# F1-chip.net
KiCad netlist of a schematic drawn in Altium Designer
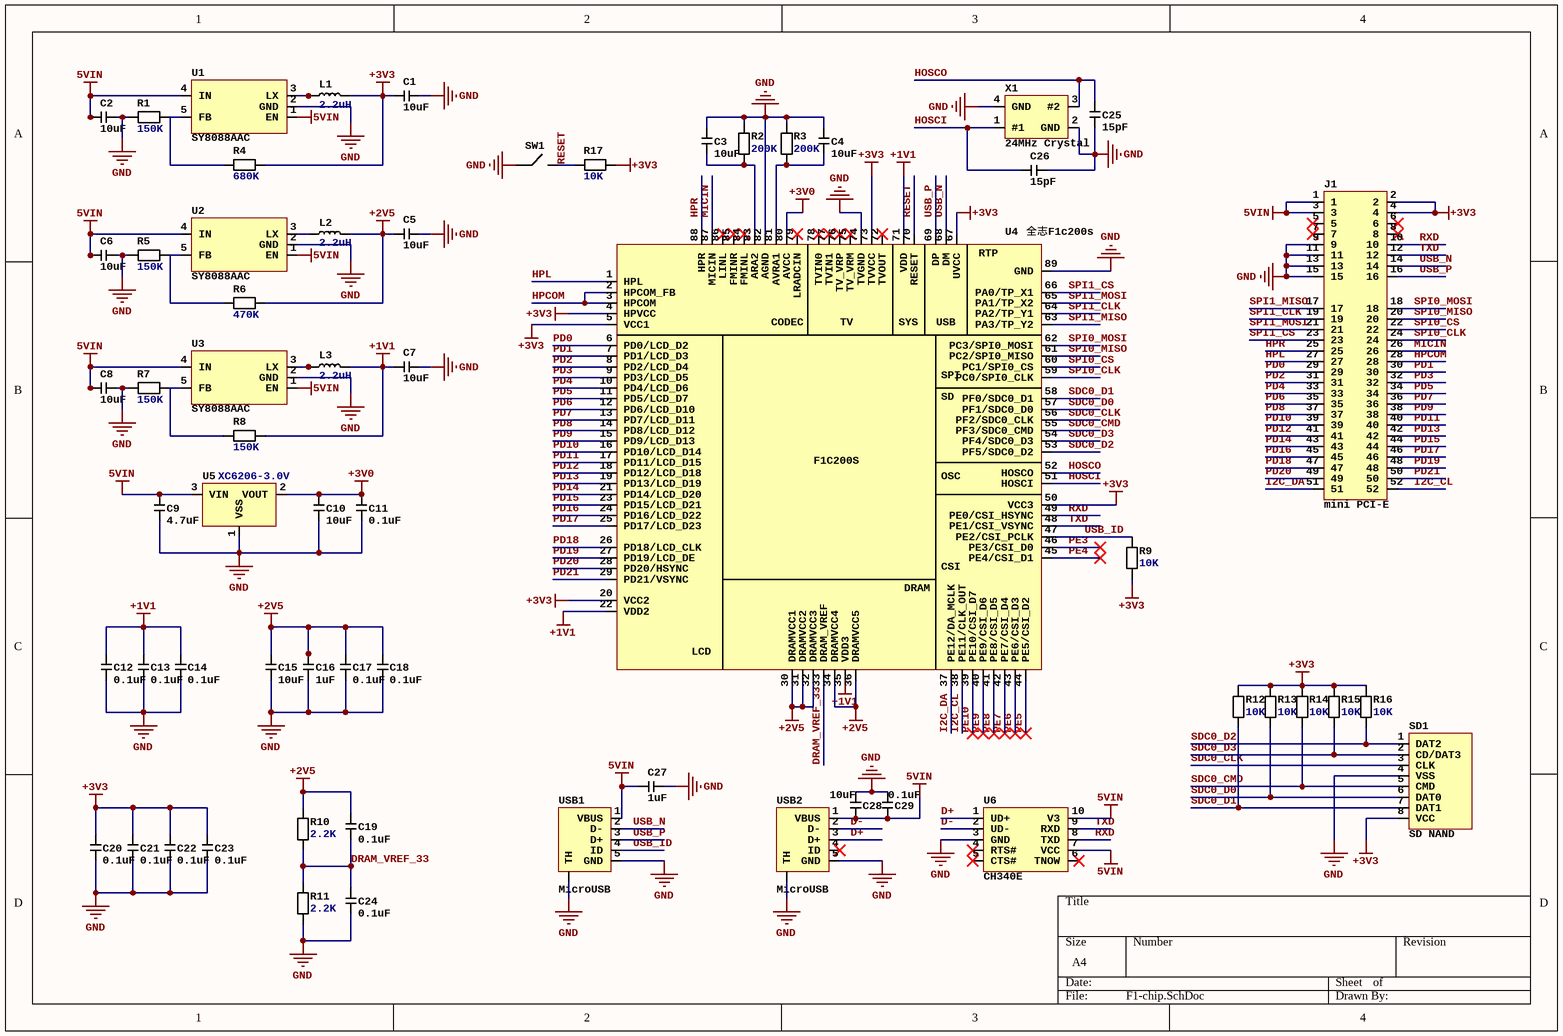
[diagram p0: F1-chip.SchDoc]

(export (version "E")
  (design (tool "Eeschema 10.0.6"))
  (components
    (comp (ref "C1")
      (value "10uF")
      (footprint "CAP_0402")
      (description "0402")
      (libsource (lib "myIntlib") (part "CAP_0402_10uF"))
    )
    (comp (ref "C2")
      (value "10uF")
      (footprint "CAP_0402")
      (description "0402")
      (libsource (lib "myIntlib") (part "CAP_0402_10uF"))
    )
    (comp (ref "C3")
      (value "10uF")
      (footprint "CAP_0402")
      (description "0402")
      (libsource (lib "myIntlib") (part "CAP_0402_10uF"))
    )
    (comp (ref "C4")
      (value "10uF")
      (footprint "CAP_0402")
      (description "0402")
      (libsource (lib "myIntlib") (part "CAP_0402_10uF"))
    )
    (comp (ref "C5")
      (value "10uF")
      (footprint "CAP_0402")
      (description "0402")
      (libsource (lib "myIntlib") (part "CAP_0402_10uF"))
    )
    (comp (ref "C6")
      (value "10uF")
      (footprint "CAP_0402")
      (description "0402")
      (libsource (lib "myIntlib") (part "CAP_0402_10uF"))
    )
    (comp (ref "C7")
      (value "10uF")
      (footprint "CAP_0402")
      (description "0402")
      (libsource (lib "myIntlib") (part "CAP_0402_10uF"))
    )
    (comp (ref "C8")
      (value "10uF")
      (footprint "CAP_0402")
      (description "0402")
      (libsource (lib "myIntlib") (part "CAP_0402_10uF"))
    )
    (comp (ref "C9")
      (value "4.7uF")
      (footprint "CAP_0402")
      (description "0402")
      (libsource (lib "myIntlib") (part "CAP_0402_4.7uF"))
    )
    (comp (ref "C10")
      (value "10uF")
      (footprint "CAP_0402")
      (description "0402")
      (libsource (lib "myIntlib") (part "CAP_0402_10uF"))
    )
    (comp (ref "C11")
      (value "0.1uF")
      (footprint "CAP_0402")
      (description "0402")
      (libsource (lib "myIntlib") (part "CAP_0402_0.1uF"))
    )
    (comp (ref "C12")
      (value "0.1uF")
      (footprint "CAP_0402")
      (description "0402")
      (libsource (lib "myIntlib") (part "CAP_0402_0.1uF"))
    )
    (comp (ref "C13")
      (value "0.1uF")
      (footprint "CAP_0402")
      (description "0402")
      (libsource (lib "myIntlib") (part "CAP_0402_0.1uF"))
    )
    (comp (ref "C14")
      (value "0.1uF")
      (footprint "CAP_0402")
      (description "0402")
      (libsource (lib "myIntlib") (part "CAP_0402_0.1uF"))
    )
    (comp (ref "C15")
      (value "10uF")
      (footprint "CAP_0402")
      (description "0402")
      (libsource (lib "myIntlib") (part "CAP_0402_10uF"))
    )
    (comp (ref "C16")
      (value "1uF")
      (footprint "CAP_0402")
      (description "0402")
      (libsource (lib "myIntlib") (part "CAP_0402_1uF"))
    )
    (comp (ref "C17")
      (value "0.1uF")
      (footprint "CAP_0402")
      (description "0402")
      (libsource (lib "myIntlib") (part "CAP_0402_0.1uF"))
    )
    (comp (ref "C18")
      (value "0.1uF")
      (footprint "CAP_0402")
      (description "0402")
      (libsource (lib "myIntlib") (part "CAP_0402_0.1uF"))
    )
    (comp (ref "C19")
      (value "0.1uF")
      (footprint "CAP_0402")
      (description "0402")
      (libsource (lib "myIntlib") (part "CAP_0402_0.1uF"))
    )
    (comp (ref "C20")
      (value "0.1uF")
      (footprint "CAP_0402")
      (description "0402")
      (libsource (lib "myIntlib") (part "CAP_0402_0.1uF"))
    )
    (comp (ref "C21")
      (value "0.1uF")
      (footprint "CAP_0402")
      (description "0402")
      (libsource (lib "myIntlib") (part "CAP_0402_0.1uF"))
    )
    (comp (ref "C22")
      (value "0.1uF")
      (footprint "CAP_0402")
      (description "0402")
      (libsource (lib "myIntlib") (part "CAP_0402_0.1uF"))
    )
    (comp (ref "C23")
      (value "0.1uF")
      (footprint "CAP_0402")
      (description "0402")
      (libsource (lib "myIntlib") (part "CAP_0402_0.1uF"))
    )
    (comp (ref "C24")
      (value "0.1uF")
      (footprint "CAP_0402")
      (description "0402")
      (libsource (lib "myIntlib") (part "CAP_0402_0.1uF"))
    )
    (comp (ref "C25")
      (value "15pF")
      (footprint "CAP_0402")
      (description "0402")
      (libsource (lib "myIntlib") (part "CAP_0402_15pF"))
    )
    (comp (ref "C26")
      (value "15pF")
      (footprint "CAP_0402")
      (description "0402")
      (libsource (lib "myIntlib") (part "CAP_0402_15pF"))
    )
    (comp (ref "C27")
      (value "1uF")
      (footprint "CAP_0402")
      (description "0402")
      (libsource (lib "myIntlib") (part "CAP_0402_1uF"))
    )
    (comp (ref "C28")
      (value "10uF")
      (footprint "CAP_0402")
      (description "0402")
      (libsource (lib "myIntlib") (part "CAP_0402_10uF"))
    )
    (comp (ref "C29")
      (value "0.1uF")
      (footprint "CAP_0402")
      (description "0402")
      (libsource (lib "myIntlib") (part "CAP_0402_0.1uF"))
    )
    (comp (ref "J1")
      (value "mini PCI-E")
      (footprint "mini PCI-E")
      (libsource (lib "myIntlib") (part "mini PCI-E"))
    )
    (comp (ref "L1")
      (value "2.2uH")
      (footprint "IND_0603")
      (description "0603")
      (libsource (lib "myIntlib") (part "IND_0603_2.2uH"))
    )
    (comp (ref "L2")
      (value "2.2uH")
      (footprint "IND_0603")
      (description "0603")
      (libsource (lib "myIntlib") (part "IND_0603_2.2uH"))
    )
    (comp (ref "L3")
      (value "2.2uH")
      (footprint "IND_0603")
      (description "0603")
      (libsource (lib "myIntlib") (part "IND_0603_2.2uH"))
    )
    (comp (ref "R1")
      (value "150K")
      (footprint "RES_0402")
      (description "0402")
      (libsource (lib "myIntlib") (part "RES_0402_150K"))
    )
    (comp (ref "R2")
      (value "200K")
      (footprint "RES_0402")
      (description "0402")
      (libsource (lib "myIntlib") (part "RES_0402_200K"))
    )
    (comp (ref "R3")
      (value "200K")
      (footprint "RES_0402")
      (description "0402")
      (libsource (lib "myIntlib") (part "RES_0402_200K"))
    )
    (comp (ref "R4")
      (value "680K")
      (footprint "RES_0402")
      (description "0402")
      (libsource (lib "myIntlib") (part "RES_0402_680K"))
    )
    (comp (ref "R5")
      (value "150K")
      (footprint "RES_0402")
      (description "0402")
      (libsource (lib "myIntlib") (part "RES_0402_150K"))
    )
    (comp (ref "R6")
      (value "470K")
      (footprint "RES_0402")
      (description "0402")
      (libsource (lib "myIntlib") (part "RES_0402_470K"))
    )
    (comp (ref "R7")
      (value "150K")
      (footprint "RES_0402")
      (description "0402")
      (libsource (lib "myIntlib") (part "RES_0402_150K"))
    )
    (comp (ref "R8")
      (value "150K")
      (footprint "RES_0402")
      (description "0402")
      (libsource (lib "myIntlib") (part "RES_0402_150K"))
    )
    (comp (ref "R9")
      (value "10K")
      (footprint "RES_0402")
      (description "0402")
      (libsource (lib "myIntlib") (part "RES_0402_10K"))
    )
    (comp (ref "R10")
      (value "2.2K")
      (footprint "RES_0402")
      (description "0402")
      (libsource (lib "myIntlib") (part "RES_0402_2.2K"))
    )
    (comp (ref "R11")
      (value "2.2K")
      (footprint "RES_0402")
      (description "0402")
      (libsource (lib "myIntlib") (part "RES_0402_2.2K"))
    )
    (comp (ref "R12")
      (value "10K")
      (footprint "RES_0402")
      (description "0402")
      (libsource (lib "myIntlib") (part "RES_0402_10K"))
    )
    (comp (ref "R13")
      (value "10K")
      (footprint "RES_0402")
      (description "0402")
      (libsource (lib "myIntlib") (part "RES_0402_10K"))
    )
    (comp (ref "R14")
      (value "10K")
      (footprint "RES_0402")
      (description "0402")
      (libsource (lib "myIntlib") (part "RES_0402_10K"))
    )
    (comp (ref "R15")
      (value "10K")
      (footprint "RES_0402")
      (description "0402")
      (libsource (lib "myIntlib") (part "RES_0402_10K"))
    )
    (comp (ref "R16")
      (value "10K")
      (footprint "RES_0402")
      (description "0402")
      (libsource (lib "myIntlib") (part "RES_0402_10K"))
    )
    (comp (ref "R17")
      (value "10K")
      (footprint "RES_0402")
      (description "0402")
      (libsource (lib "myIntlib") (part "RES_0402_10K"))
    )
    (comp (ref "SD1") (value "SD NAND") (footprint "SD NAND") (libsource (lib "myIntlib") (part "SD NAND")))
    (comp (ref "SW1")
      (value "贴片按钮")
      (footprint "BUTTON2")
      (description "3*4*2两脚小龟贴片按钮")
      (libsource (lib "myIntlib") (part "贴片按钮"))
    )
    (comp (ref "U1")
      (value "SY8088AAC")
      (footprint "SY8088AAC")
      (description "SOT23-5")
      (libsource (lib "myIntlib") (part "SY8088AAC"))
    )
    (comp (ref "U2")
      (value "SY8088AAC")
      (footprint "SY8088AAC")
      (description "SOT23-5")
      (libsource (lib "myIntlib") (part "SY8088AAC"))
    )
    (comp (ref "U3")
      (value "SY8088AAC")
      (footprint "SY8088AAC")
      (description "SOT23-5")
      (libsource (lib "myIntlib") (part "SY8088AAC"))
    )
    (comp (ref "U4")
      (value "全志F1c200s")
      (footprint "F1c200s")
      (description "MQFN-88")
      (libsource (lib "myIntlib") (part "F1c200s"))
    )
    (comp (ref "U5")
      (value "XC6206-3.0V")
      (footprint "XC6206")
      (description "SOT23-3")
      (libsource (lib "myIntlib") (part "XC6206-3.0V"))
    )
    (comp (ref "U6")
      (value "CH340E")
      (footprint "CH340E")
      (description "MSOP-10")
      (libsource (lib "myIntlib") (part "CH340E"))
    )
    (comp (ref "USB1")
      (value "MicroUSB")
      (footprint "MicroUSB")
      (libsource (lib "myIntlib") (part "MicroUSB"))
    )
    (comp (ref "USB2")
      (value "MicroUSB")
      (footprint "MicroUSB")
      (libsource (lib "myIntlib") (part "MicroUSB"))
    )
    (comp (ref "X1")
      (value "24MHz Crystal")
      (footprint "SMD3225")
      (description "SMD3225")
      (libsource (lib "myIntlib") (part "24MHz Crystal"))
    )
  )
  (nets
    (net (code "1") (name "+1V1") (class "Default")
      (node (ref "C12") (pin "2") (pinfunction "2_2") (pintype "passive"))
      (node (ref "C13") (pin "2") (pinfunction "2_2") (pintype "passive"))
      (node (ref "C14") (pin "2") (pinfunction "2_2") (pintype "passive"))
      (node (ref "C7") (pin "1") (pinfunction "1_1") (pintype "passive"))
      (node (ref "L3") (pin "2") (pinfunction "2_2") (pintype "passive"))
      (node (ref "R8") (pin "2") (pinfunction "2_2") (pintype "passive"))
      (node (ref "U4") (pin "22") (pinfunction "VDD2_22") (pintype "passive"))
      (node (ref "U4") (pin "35") (pinfunction "VDD3_35") (pintype "passive"))
      (node (ref "U4") (pin "71") (pinfunction "VDD_71") (pintype "passive"))
    )
    (net (code "2") (name "+2V5") (class "Default")
      (node (ref "C15") (pin "2") (pinfunction "2_2") (pintype "passive"))
      (node (ref "C16") (pin "2") (pinfunction "2_2") (pintype "passive"))
      (node (ref "C17") (pin "2") (pinfunction "2_2") (pintype "passive"))
      (node (ref "C18") (pin "2") (pinfunction "2_2") (pintype "passive"))
      (node (ref "C19") (pin "2") (pinfunction "2_2") (pintype "passive"))
      (node (ref "C5") (pin "1") (pinfunction "1_1") (pintype "passive"))
      (node (ref "L2") (pin "2") (pinfunction "2_2") (pintype "passive"))
      (node (ref "R10") (pin "2") (pinfunction "2_2") (pintype "passive"))
      (node (ref "R6") (pin "2") (pinfunction "2_2") (pintype "passive"))
      (node (ref "U4") (pin "30") (pinfunction "DRAMVCC1_30") (pintype "passive"))
      (node (ref "U4") (pin "31") (pinfunction "DRAMVCC2_31") (pintype "passive"))
      (node (ref "U4") (pin "32") (pinfunction "DRAMVCC3_32") (pintype "passive"))
      (node (ref "U4") (pin "34") (pinfunction "DRAMVCC4_34") (pintype "passive"))
      (node (ref "U4") (pin "36") (pinfunction "DRAMVCC5_36") (pintype "passive"))
    )
    (net (code "3") (name "+3V0") (class "Default")
      (node (ref "C10") (pin "2") (pinfunction "2_2") (pintype "passive"))
      (node (ref "C11") (pin "2") (pinfunction "2_2") (pintype "passive"))
      (node (ref "U4") (pin "80") (pinfunction "AVCC_80") (pintype "passive"))
      (node (ref "U5") (pin "2") (pinfunction "VOUT_2") (pintype "passive"))
    )
    (net (code "4") (name "+3V3") (class "Default")
      (node (ref "C1") (pin "1") (pinfunction "1_1") (pintype "passive"))
      (node (ref "C20") (pin "2") (pinfunction "2_2") (pintype "passive"))
      (node (ref "C21") (pin "2") (pinfunction "2_2") (pintype "passive"))
      (node (ref "C22") (pin "2") (pinfunction "2_2") (pintype "passive"))
      (node (ref "C23") (pin "2") (pinfunction "2_2") (pintype "passive"))
      (node (ref "J1") (pin "2") (pinfunction "2_2") (pintype "passive"))
      (node (ref "J1") (pin "4") (pinfunction "4_4") (pintype "passive"))
      (node (ref "L1") (pin "2") (pinfunction "2_2") (pintype "passive"))
      (node (ref "R12") (pin "2") (pinfunction "2_2") (pintype "passive"))
      (node (ref "R13") (pin "2") (pinfunction "2_2") (pintype "passive"))
      (node (ref "R14") (pin "2") (pinfunction "2_2") (pintype "passive"))
      (node (ref "R15") (pin "2") (pinfunction "2_2") (pintype "passive"))
      (node (ref "R16") (pin "2") (pinfunction "2_2") (pintype "passive"))
      (node (ref "R17") (pin "2") (pinfunction "2_2") (pintype "passive"))
      (node (ref "R4") (pin "2") (pinfunction "2_2") (pintype "passive"))
      (node (ref "R9") (pin "1") (pinfunction "1_1") (pintype "passive"))
      (node (ref "SD1") (pin "8") (pinfunction "VCC_8") (pintype "passive"))
      (node (ref "U4") (pin "20") (pinfunction "VCC2_20") (pintype "passive"))
      (node (ref "U4") (pin "4") (pinfunction "HPVCC_4") (pintype "passive"))
      (node (ref "U4") (pin "5") (pinfunction "VCC1_5") (pintype "passive"))
      (node (ref "U4") (pin "50") (pinfunction "VCC3_50") (pintype "passive"))
      (node (ref "U4") (pin "67") (pinfunction "UVCC_67") (pintype "passive"))
      (node (ref "U4") (pin "73") (pinfunction "TVVCC_73") (pintype "passive"))
    )
    (net (code "5") (name "/D+") (class "Default")
      (node (ref "U6") (pin "1") (pinfunction "UD+_1") (pintype "passive"))
      (node (ref "USB2") (pin "3") (pinfunction "D+_3") (pintype "passive"))
    )
    (net (code "6") (name "/D-") (class "Default")
      (node (ref "U6") (pin "2") (pinfunction "UD-_2") (pintype "passive"))
      (node (ref "USB2") (pin "2") (pinfunction "D-_2") (pintype "passive"))
    )
    (net (code "7") (name "/DRAM_VREF_33") (class "Default")
      (node (ref "C19") (pin "1") (pinfunction "1_1") (pintype "passive"))
      (node (ref "C24") (pin "2") (pinfunction "2_2") (pintype "passive"))
      (node (ref "R10") (pin "1") (pinfunction "1_1") (pintype "passive"))
      (node (ref "R11") (pin "2") (pinfunction "2_2") (pintype "passive"))
      (node (ref "U4") (pin "33") (pinfunction "DRAM_VREF_33") (pintype "passive"))
    )
    (net (code "8") (name "/HOSCI") (class "Default")
      (node (ref "C26") (pin "1") (pinfunction "1_1") (pintype "passive"))
      (node (ref "U4") (pin "51") (pinfunction "HOSCI_51") (pintype "passive"))
      (node (ref "X1") (pin "1") (pinfunction "#1_1") (pintype "passive"))
    )
    (net (code "9") (name "/HOSCO") (class "Default")
      (node (ref "C25") (pin "2") (pinfunction "2_2") (pintype "passive"))
      (node (ref "U4") (pin "52") (pinfunction "HOSCO_52") (pintype "passive"))
      (node (ref "X1") (pin "3") (pinfunction "#2_3") (pintype "passive"))
    )
    (net (code "10") (name "/HPCOM") (class "Default")
      (node (ref "J1") (pin "28") (pinfunction "28_28") (pintype "passive"))
      (node (ref "U4") (pin "2") (pinfunction "HPCOM_FB_2") (pintype "passive"))
      (node (ref "U4") (pin "3") (pinfunction "HPCOM_3") (pintype "passive"))
    )
    (net (code "11") (name "/HPL") (class "Default")
      (node (ref "J1") (pin "27") (pinfunction "27_27") (pintype "passive"))
      (node (ref "U4") (pin "1") (pinfunction "HPL_1") (pintype "passive"))
    )
    (net (code "12") (name "/HPR") (class "Default")
      (node (ref "J1") (pin "25") (pinfunction "25_25") (pintype "passive"))
      (node (ref "U4") (pin "88") (pinfunction "HPR_88") (pintype "passive"))
    )
    (net (code "13") (name "/I2C_CL") (class "Default")
      (node (ref "J1") (pin "52") (pinfunction "52_52") (pintype "passive"))
      (node (ref "U4") (pin "38") (pinfunction "PE11/CLK_OUT_38") (pintype "passive"))
    )
    (net (code "14") (name "/I2C_DA") (class "Default")
      (node (ref "J1") (pin "51") (pinfunction "51_51") (pintype "passive"))
      (node (ref "U4") (pin "37") (pinfunction "PE12/DA_MCLK_37") (pintype "passive"))
    )
    (net (code "15") (name "/MICIN") (class "Default")
      (node (ref "J1") (pin "26") (pinfunction "26_26") (pintype "passive"))
      (node (ref "U4") (pin "87") (pinfunction "MICIN_87") (pintype "passive"))
    )
    (net (code "16") (name "/PD0") (class "Default")
      (node (ref "J1") (pin "29") (pinfunction "29_29") (pintype "passive"))
      (node (ref "U4") (pin "6") (pinfunction "PD0/LCD_D2_6") (pintype "passive"))
    )
    (net (code "17") (name "/PD1") (class "Default")
      (node (ref "J1") (pin "30") (pinfunction "30_30") (pintype "passive"))
      (node (ref "U4") (pin "7") (pinfunction "PD1/LCD_D3_7") (pintype "passive"))
    )
    (net (code "18") (name "/PD2") (class "Default")
      (node (ref "J1") (pin "31") (pinfunction "31_31") (pintype "passive"))
      (node (ref "U4") (pin "8") (pinfunction "PD2/LCD_D4_8") (pintype "passive"))
    )
    (net (code "19") (name "/PD3") (class "Default")
      (node (ref "J1") (pin "32") (pinfunction "32_32") (pintype "passive"))
      (node (ref "U4") (pin "9") (pinfunction "PD3/LCD_D5_9") (pintype "passive"))
    )
    (net (code "20") (name "/PD4") (class "Default")
      (node (ref "J1") (pin "33") (pinfunction "33_33") (pintype "passive"))
      (node (ref "U4") (pin "10") (pinfunction "PD4/LCD_D6_10") (pintype "passive"))
    )
    (net (code "21") (name "/PD5") (class "Default")
      (node (ref "J1") (pin "34") (pinfunction "34_34") (pintype "passive"))
      (node (ref "U4") (pin "11") (pinfunction "PD5/LCD_D7_11") (pintype "passive"))
    )
    (net (code "22") (name "/PD6") (class "Default")
      (node (ref "J1") (pin "35") (pinfunction "35_35") (pintype "passive"))
      (node (ref "U4") (pin "12") (pinfunction "PD6/LCD_D10_12") (pintype "passive"))
    )
    (net (code "23") (name "/PD7") (class "Default")
      (node (ref "J1") (pin "36") (pinfunction "36_36") (pintype "passive"))
      (node (ref "U4") (pin "13") (pinfunction "PD7/LCD_D11_13") (pintype "passive"))
    )
    (net (code "24") (name "/PD8") (class "Default")
      (node (ref "J1") (pin "37") (pinfunction "37_37") (pintype "passive"))
      (node (ref "U4") (pin "14") (pinfunction "PD8/LCD_D12_14") (pintype "passive"))
    )
    (net (code "25") (name "/PD9") (class "Default")
      (node (ref "J1") (pin "38") (pinfunction "38_38") (pintype "passive"))
      (node (ref "U4") (pin "15") (pinfunction "PD9/LCD_D13_15") (pintype "passive"))
    )
    (net (code "26") (name "/PD10") (class "Default")
      (node (ref "J1") (pin "39") (pinfunction "39_39") (pintype "passive"))
      (node (ref "U4") (pin "16") (pinfunction "PD10/LCD_D14_16") (pintype "passive"))
    )
    (net (code "27") (name "/PD11") (class "Default")
      (node (ref "J1") (pin "40") (pinfunction "40_40") (pintype "passive"))
      (node (ref "U4") (pin "17") (pinfunction "PD11/LCD_D15_17") (pintype "passive"))
    )
    (net (code "28") (name "/PD12") (class "Default")
      (node (ref "J1") (pin "41") (pinfunction "41_41") (pintype "passive"))
      (node (ref "U4") (pin "18") (pinfunction "PD12/LCD_D18_18") (pintype "passive"))
    )
    (net (code "29") (name "/PD13") (class "Default")
      (node (ref "J1") (pin "42") (pinfunction "42_42") (pintype "passive"))
      (node (ref "U4") (pin "19") (pinfunction "PD13/LCD_D19_19") (pintype "passive"))
    )
    (net (code "30") (name "/PD14") (class "Default")
      (node (ref "J1") (pin "43") (pinfunction "43_43") (pintype "passive"))
      (node (ref "U4") (pin "21") (pinfunction "PD14/LCD_D20_21") (pintype "passive"))
    )
    (net (code "31") (name "/PD15") (class "Default")
      (node (ref "J1") (pin "44") (pinfunction "44_44") (pintype "passive"))
      (node (ref "U4") (pin "23") (pinfunction "PD15/LCD_D21_23") (pintype "passive"))
    )
    (net (code "32") (name "/PD16") (class "Default")
      (node (ref "J1") (pin "45") (pinfunction "45_45") (pintype "passive"))
      (node (ref "U4") (pin "24") (pinfunction "PD16/LCD_D22_24") (pintype "passive"))
    )
    (net (code "33") (name "/PD17") (class "Default")
      (node (ref "J1") (pin "46") (pinfunction "46_46") (pintype "passive"))
      (node (ref "U4") (pin "25") (pinfunction "PD17/LCD_D23_25") (pintype "passive"))
    )
    (net (code "34") (name "/PD18") (class "Default")
      (node (ref "J1") (pin "47") (pinfunction "47_47") (pintype "passive"))
      (node (ref "U4") (pin "26") (pinfunction "PD18/LCD_CLK_26") (pintype "passive"))
    )
    (net (code "35") (name "/PD19") (class "Default")
      (node (ref "J1") (pin "48") (pinfunction "48_48") (pintype "passive"))
      (node (ref "U4") (pin "27") (pinfunction "PD19/LCD_DE_27") (pintype "passive"))
    )
    (net (code "36") (name "/PD20") (class "Default")
      (node (ref "J1") (pin "49") (pinfunction "49_49") (pintype "passive"))
      (node (ref "U4") (pin "28") (pinfunction "PD20/HSYNC_28") (pintype "passive"))
    )
    (net (code "37") (name "/PD21") (class "Default")
      (node (ref "J1") (pin "50") (pinfunction "50_50") (pintype "passive"))
      (node (ref "U4") (pin "29") (pinfunction "PD21/VSYNC_29") (pintype "passive"))
    )
    (net (code "38") (name "/PE3") (class "Default")
      (node (ref "U4") (pin "46") (pinfunction "PE3/CSI_D0_46") (pintype "passive+no_connect"))
    )
    (net (code "39") (name "/PE4") (class "Default")
      (node (ref "U4") (pin "45") (pinfunction "PE4/CSI_D1_45") (pintype "passive+no_connect"))
    )
    (net (code "40") (name "/PE5") (class "Default")
      (node (ref "U4") (pin "44") (pinfunction "PE5/CSI_D2_44") (pintype "passive+no_connect"))
    )
    (net (code "41") (name "/PE6") (class "Default")
      (node (ref "U4") (pin "43") (pinfunction "PE6/CSI_D3_43") (pintype "passive+no_connect"))
    )
    (net (code "42") (name "/PE7") (class "Default")
      (node (ref "U4") (pin "42") (pinfunction "PE7/CSI_D4_42") (pintype "passive+no_connect"))
    )
    (net (code "43") (name "/PE8") (class "Default")
      (node (ref "U4") (pin "41") (pinfunction "PE8/CSI_D5_41") (pintype "passive+no_connect"))
    )
    (net (code "44") (name "/PE9") (class "Default")
      (node (ref "U4") (pin "40") (pinfunction "PE9/CSI_D6_40") (pintype "passive+no_connect"))
    )
    (net (code "45") (name "/PE10") (class "Default")
      (node (ref "U4") (pin "39") (pinfunction "PE10/CSI_D7_39") (pintype "passive+no_connect"))
    )
    (net (code "46") (name "/RESET") (class "Default")
      (node (ref "R17") (pin "1") (pinfunction "1_1") (pintype "passive"))
      (node (ref "SW1") (pin "2") (pintype "passive"))
      (node (ref "U4") (pin "70") (pinfunction "RESET_70") (pintype "passive"))
    )
    (net (code "47") (name "/RXD") (class "Default")
      (node (ref "J1") (pin "10") (pinfunction "10_10") (pintype "passive"))
      (node (ref "U4") (pin "49") (pinfunction "PE0/CSI_HSYNC_49") (pintype "passive"))
      (node (ref "U6") (pin "8") (pinfunction "TXD_8") (pintype "passive"))
    )
    (net (code "48") (name "/SDC0_CLK") (class "Default")
      (node (ref "SD1") (pin "3") (pinfunction "CLK_3") (pintype "passive"))
      (node (ref "U4") (pin "56") (pinfunction "PF2/SDC0_CLK_56") (pintype "passive"))
    )
    (net (code "49") (name "/SDC0_CMD") (class "Default")
      (node (ref "R14") (pin "1") (pinfunction "1_1") (pintype "passive"))
      (node (ref "SD1") (pin "5") (pinfunction "CMD_5") (pintype "passive"))
      (node (ref "U4") (pin "55") (pinfunction "PF3/SDC0_CMD_55") (pintype "passive"))
    )
    (net (code "50") (name "/SDC0_D0") (class "Default")
      (node (ref "R13") (pin "1") (pinfunction "1_1") (pintype "passive"))
      (node (ref "SD1") (pin "6") (pinfunction "DAT0_6") (pintype "passive"))
      (node (ref "U4") (pin "57") (pinfunction "PF1/SDC0_D0_57") (pintype "passive"))
    )
    (net (code "51") (name "/SDC0_D1") (class "Default")
      (node (ref "R12") (pin "1") (pinfunction "1_1") (pintype "passive"))
      (node (ref "SD1") (pin "7") (pinfunction "DAT1_7") (pintype "passive"))
      (node (ref "U4") (pin "58") (pinfunction "PF0/SDC0_D1_58") (pintype "passive"))
    )
    (net (code "52") (name "/SDC0_D2") (class "Default")
      (node (ref "R16") (pin "1") (pinfunction "1_1") (pintype "passive"))
      (node (ref "SD1") (pin "1") (pinfunction "DAT2_1") (pintype "passive"))
      (node (ref "U4") (pin "53") (pinfunction "PF5/SDC0_D2_53") (pintype "passive"))
    )
    (net (code "53") (name "/SDC0_D3") (class "Default")
      (node (ref "R15") (pin "1") (pinfunction "1_1") (pintype "passive"))
      (node (ref "SD1") (pin "2") (pinfunction "CD/DAT3_2") (pintype "passive"))
      (node (ref "U4") (pin "54") (pinfunction "PF4/SDC0_D3_54") (pintype "passive"))
    )
    (net (code "54") (name "/SPI0_CLK") (class "Default")
      (node (ref "J1") (pin "24") (pinfunction "24_24") (pintype "passive"))
      (node (ref "U4") (pin "59") (pinfunction "PC0/SPI0_CLK_59") (pintype "passive"))
    )
    (net (code "55") (name "/SPI0_CS") (class "Default")
      (node (ref "J1") (pin "22") (pinfunction "22_22") (pintype "passive"))
      (node (ref "U4") (pin "60") (pinfunction "PC1/SPI0_CS_60") (pintype "passive"))
    )
    (net (code "56") (name "/SPI0_MISO") (class "Default")
      (node (ref "J1") (pin "20") (pinfunction "20_20") (pintype "passive"))
      (node (ref "U4") (pin "61") (pinfunction "PC2/SPI0_MISO_61") (pintype "passive"))
    )
    (net (code "57") (name "/SPI0_MOSI") (class "Default")
      (node (ref "J1") (pin "18") (pinfunction "18_18") (pintype "passive"))
      (node (ref "U4") (pin "62") (pinfunction "PC3/SPI0_MOSI_62") (pintype "passive"))
    )
    (net (code "58") (name "/SPI1_CLK") (class "Default")
      (node (ref "J1") (pin "19") (pinfunction "19_19") (pintype "passive"))
      (node (ref "U4") (pin "64") (pinfunction "PA2/TP_Y1_64") (pintype "passive"))
    )
    (net (code "59") (name "/SPI1_CS") (class "Default")
      (node (ref "J1") (pin "23") (pinfunction "23_23") (pintype "passive"))
      (node (ref "U4") (pin "66") (pinfunction "PA0/TP_X1_66") (pintype "passive"))
    )
    (net (code "60") (name "/SPI1_MISO") (class "Default")
      (node (ref "J1") (pin "17") (pinfunction "17_17") (pintype "passive"))
      (node (ref "U4") (pin "63") (pinfunction "PA3/TP_Y2_63") (pintype "passive"))
    )
    (net (code "61") (name "/SPI1_MOSI") (class "Default")
      (node (ref "J1") (pin "21") (pinfunction "21_21") (pintype "passive"))
      (node (ref "U4") (pin "65") (pinfunction "PA1/TP_X2_65") (pintype "passive"))
    )
    (net (code "62") (name "/TXD") (class "Default")
      (node (ref "J1") (pin "12") (pinfunction "12_12") (pintype "passive"))
      (node (ref "U4") (pin "48") (pinfunction "PE1/CSI_VSYNC_48") (pintype "passive"))
      (node (ref "U6") (pin "9") (pinfunction "RXD_9") (pintype "passive"))
    )
    (net (code "63") (name "/USB_ID") (class "Default")
      (node (ref "R9") (pin "2") (pinfunction "2_2") (pintype "passive"))
      (node (ref "U4") (pin "47") (pinfunction "PE2/CSI_PCLK_47") (pintype "passive"))
      (node (ref "USB1") (pin "4") (pinfunction "ID_4") (pintype "passive"))
    )
    (net (code "64") (name "/USB_N") (class "Default")
      (node (ref "J1") (pin "14") (pinfunction "14_14") (pintype "passive"))
      (node (ref "U4") (pin "68") (pinfunction "DM_68") (pintype "passive"))
      (node (ref "USB1") (pin "2") (pinfunction "D-_2") (pintype "passive"))
    )
    (net (code "65") (name "/USB_P") (class "Default")
      (node (ref "J1") (pin "16") (pinfunction "16_16") (pintype "passive"))
      (node (ref "U4") (pin "69") (pinfunction "DP_69") (pintype "passive"))
      (node (ref "USB1") (pin "3") (pinfunction "D+_3") (pintype "passive"))
    )
    (net (code "66") (name "5VIN") (class "Default")
      (node (ref "C2") (pin "1") (pinfunction "1_1") (pintype "passive"))
      (node (ref "C27") (pin "1") (pinfunction "1_1") (pintype "passive"))
      (node (ref "C28") (pin "1") (pinfunction "1_1") (pintype "passive"))
      (node (ref "C29") (pin "1") (pinfunction "1_1") (pintype "passive"))
      (node (ref "C6") (pin "1") (pinfunction "1_1") (pintype "passive"))
      (node (ref "C8") (pin "1") (pinfunction "1_1") (pintype "passive"))
      (node (ref "C9") (pin "2") (pinfunction "2_2") (pintype "passive"))
      (node (ref "J1") (pin "1") (pinfunction "1_1") (pintype "passive"))
      (node (ref "J1") (pin "3") (pinfunction "3_3") (pintype "passive"))
      (node (ref "U1") (pin "1") (pinfunction "EN_1") (pintype "passive"))
      (node (ref "U1") (pin "4") (pinfunction "IN_4") (pintype "passive"))
      (node (ref "U2") (pin "1") (pinfunction "EN_1") (pintype "passive"))
      (node (ref "U2") (pin "4") (pinfunction "IN_4") (pintype "passive"))
      (node (ref "U3") (pin "1") (pinfunction "EN_1") (pintype "passive"))
      (node (ref "U3") (pin "4") (pinfunction "IN_4") (pintype "passive"))
      (node (ref "U5") (pin "3") (pinfunction "VIN_3") (pintype "passive"))
      (node (ref "U6") (pin "10") (pinfunction "V3_10") (pintype "passive"))
      (node (ref "U6") (pin "7") (pinfunction "VCC_7") (pintype "passive"))
      (node (ref "USB1") (pin "1") (pinfunction "VBUS_1") (pintype "passive"))
      (node (ref "USB2") (pin "1") (pinfunction "VBUS_1") (pintype "passive"))
    )
    (net (code "67") (name "GND") (class "Default")
      (node (ref "C1") (pin "2") (pinfunction "2_2") (pintype "passive"))
      (node (ref "C10") (pin "1") (pinfunction "1_1") (pintype "passive"))
      (node (ref "C11") (pin "1") (pinfunction "1_1") (pintype "passive"))
      (node (ref "C12") (pin "1") (pinfunction "1_1") (pintype "passive"))
      (node (ref "C13") (pin "1") (pinfunction "1_1") (pintype "passive"))
      (node (ref "C14") (pin "1") (pinfunction "1_1") (pintype "passive"))
      (node (ref "C15") (pin "1") (pinfunction "1_1") (pintype "passive"))
      (node (ref "C16") (pin "1") (pinfunction "1_1") (pintype "passive"))
      (node (ref "C17") (pin "1") (pinfunction "1_1") (pintype "passive"))
      (node (ref "C18") (pin "1") (pinfunction "1_1") (pintype "passive"))
      (node (ref "C2") (pin "2") (pinfunction "2_2") (pintype "passive"))
      (node (ref "C20") (pin "1") (pinfunction "1_1") (pintype "passive"))
      (node (ref "C21") (pin "1") (pinfunction "1_1") (pintype "passive"))
      (node (ref "C22") (pin "1") (pinfunction "1_1") (pintype "passive"))
      (node (ref "C23") (pin "1") (pinfunction "1_1") (pintype "passive"))
      (node (ref "C24") (pin "1") (pinfunction "1_1") (pintype "passive"))
      (node (ref "C25") (pin "1") (pinfunction "1_1") (pintype "passive"))
      (node (ref "C26") (pin "2") (pinfunction "2_2") (pintype "passive"))
      (node (ref "C27") (pin "2") (pinfunction "2_2") (pintype "passive"))
      (node (ref "C28") (pin "2") (pinfunction "2_2") (pintype "passive"))
      (node (ref "C29") (pin "2") (pinfunction "2_2") (pintype "passive"))
      (node (ref "C3") (pin "2") (pinfunction "2_2") (pintype "passive"))
      (node (ref "C4") (pin "2") (pinfunction "2_2") (pintype "passive"))
      (node (ref "C5") (pin "2") (pinfunction "2_2") (pintype "passive"))
      (node (ref "C6") (pin "2") (pinfunction "2_2") (pintype "passive"))
      (node (ref "C7") (pin "2") (pinfunction "2_2") (pintype "passive"))
      (node (ref "C8") (pin "2") (pinfunction "2_2") (pintype "passive"))
      (node (ref "C9") (pin "1") (pinfunction "1_1") (pintype "passive"))
      (node (ref "J1") (pin "11") (pinfunction "11_11") (pintype "passive"))
      (node (ref "J1") (pin "13") (pinfunction "13_13") (pintype "passive"))
      (node (ref "J1") (pin "15") (pinfunction "15_15") (pintype "passive"))
      (node (ref "J1") (pin "9") (pinfunction "9_9") (pintype "passive"))
      (node (ref "R1") (pin "1") (pinfunction "1_1") (pintype "passive"))
      (node (ref "R11") (pin "1") (pinfunction "1_1") (pintype "passive"))
      (node (ref "R2") (pin "2") (pinfunction "2_2") (pintype "passive"))
      (node (ref "R3") (pin "2") (pinfunction "2_2") (pintype "passive"))
      (node (ref "R5") (pin "1") (pinfunction "1_1") (pintype "passive"))
      (node (ref "R7") (pin "1") (pinfunction "1_1") (pintype "passive"))
      (node (ref "SD1") (pin "4") (pinfunction "VSS_4") (pintype "passive"))
      (node (ref "SW1") (pin "1") (pintype "passive"))
      (node (ref "U1") (pin "2") (pinfunction "GND_2") (pintype "passive"))
      (node (ref "U2") (pin "2") (pinfunction "GND_2") (pintype "passive"))
      (node (ref "U3") (pin "2") (pinfunction "GND_2") (pintype "passive"))
      (node (ref "U4") (pin "74") (pinfunction "TVGND_74") (pintype "passive"))
      (node (ref "U4") (pin "82") (pinfunction "AGND_82") (pintype "passive"))
      (node (ref "U4") (pin "89") (pinfunction "GND_89") (pintype "passive"))
      (node (ref "U5") (pin "1") (pinfunction "VSS_1") (pintype "passive"))
      (node (ref "U6") (pin "3") (pinfunction "GND_3") (pintype "passive"))
      (node (ref "USB1") (pin "0") (pinfunction "TH_0") (pintype "passive"))
      (node (ref "USB1") (pin "5") (pinfunction "GND_5") (pintype "passive"))
      (node (ref "USB2") (pin "0") (pinfunction "TH_0") (pintype "passive"))
      (node (ref "USB2") (pin "5") (pinfunction "GND_5") (pintype "passive"))
      (node (ref "X1") (pin "2") (pinfunction "GND_2") (pintype "passive"))
      (node (ref "X1") (pin "4") (pinfunction "GND_4") (pintype "passive"))
    )
    (net (code "68") (name "Net-(U1-FB)") (class "Default")
      (node (ref "R1") (pin "2") (pinfunction "2_2") (pintype "passive"))
      (node (ref "R4") (pin "1") (pinfunction "1_1") (pintype "passive"))
      (node (ref "U1") (pin "5") (pinfunction "FB_5") (pintype "passive"))
    )
    (net (code "69") (name "Net-(U1-LX)") (class "Default")
      (node (ref "L1") (pin "1") (pinfunction "1_1") (pintype "passive"))
      (node (ref "U1") (pin "3") (pinfunction "LX_3") (pintype "passive"))
    )
    (net (code "70") (name "Net-(U2-FB)") (class "Default")
      (node (ref "R5") (pin "2") (pinfunction "2_2") (pintype "passive"))
      (node (ref "R6") (pin "1") (pinfunction "1_1") (pintype "passive"))
      (node (ref "U2") (pin "5") (pinfunction "FB_5") (pintype "passive"))
    )
    (net (code "71") (name "Net-(U2-LX)") (class "Default")
      (node (ref "L2") (pin "1") (pinfunction "1_1") (pintype "passive"))
      (node (ref "U2") (pin "3") (pinfunction "LX_3") (pintype "passive"))
    )
    (net (code "72") (name "Net-(U3-FB)") (class "Default")
      (node (ref "R7") (pin "2") (pinfunction "2_2") (pintype "passive"))
      (node (ref "R8") (pin "1") (pinfunction "1_1") (pintype "passive"))
      (node (ref "U3") (pin "5") (pinfunction "FB_5") (pintype "passive"))
    )
    (net (code "73") (name "Net-(U3-LX)") (class "Default")
      (node (ref "L3") (pin "1") (pinfunction "1_1") (pintype "passive"))
      (node (ref "U3") (pin "3") (pinfunction "LX_3") (pintype "passive"))
    )
    (net (code "74") (name "Net-(U4-ARA2)") (class "Default")
      (node (ref "C3") (pin "1") (pinfunction "1_1") (pintype "passive"))
      (node (ref "R2") (pin "1") (pinfunction "1_1") (pintype "passive"))
      (node (ref "U4") (pin "83") (pinfunction "ARA2_83") (pintype "passive"))
    )
    (net (code "75") (name "Net-(U4-AVRA1)") (class "Default")
      (node (ref "C4") (pin "1") (pinfunction "1_1") (pintype "passive"))
      (node (ref "R3") (pin "1") (pinfunction "1_1") (pintype "passive"))
      (node (ref "U4") (pin "81") (pinfunction "AVRA1_81") (pintype "passive"))
    )
    (net (code "76") (name "unconnected-(J1-Pad5)") (class "Default")
      (node (ref "J1") (pin "5") (pinfunction "5_5") (pintype "passive+no_connect"))
    )
    (net (code "77") (name "unconnected-(J1-Pad6)") (class "Default")
      (node (ref "J1") (pin "6") (pinfunction "6_6") (pintype "passive+no_connect"))
    )
    (net (code "78") (name "unconnected-(J1-Pad7)") (class "Default")
      (node (ref "J1") (pin "7") (pinfunction "7_7") (pintype "passive+no_connect"))
    )
    (net (code "79") (name "unconnected-(J1-Pad8)") (class "Default")
      (node (ref "J1") (pin "8") (pinfunction "8_8") (pintype "passive+no_connect"))
    )
    (net (code "80") (name "unconnected-(U4-FMINL-Pad84)") (class "Default")
      (node (ref "U4") (pin "84") (pinfunction "FMINL_84") (pintype "passive+no_connect"))
    )
    (net (code "81") (name "unconnected-(U4-FMINR-Pad85)") (class "Default")
      (node (ref "U4") (pin "85") (pinfunction "FMINR_85") (pintype "passive+no_connect"))
    )
    (net (code "82") (name "unconnected-(U4-LINL-Pad86)") (class "Default")
      (node (ref "U4") (pin "86") (pinfunction "LINL_86") (pintype "passive+no_connect"))
    )
    (net (code "83") (name "unconnected-(U4-LRADCIN-Pad79)") (class "Default")
      (node (ref "U4") (pin "79") (pinfunction "LRADCIN_79") (pintype "passive+no_connect"))
    )
    (net (code "84") (name "unconnected-(U4-TVIN0-Pad78)") (class "Default")
      (node (ref "U4") (pin "78") (pinfunction "TVIN0_78") (pintype "passive+no_connect"))
    )
    (net (code "85") (name "unconnected-(U4-TVIN1-Pad77)") (class "Default")
      (node (ref "U4") (pin "77") (pinfunction "TVIN1_77") (pintype "passive+no_connect"))
    )
    (net (code "86") (name "unconnected-(U4-TVOUT-Pad72)") (class "Default")
      (node (ref "U4") (pin "72") (pinfunction "TVOUT_72") (pintype "passive+no_connect"))
    )
    (net (code "87") (name "unconnected-(U4-TV_VRM-Pad75)") (class "Default")
      (node (ref "U4") (pin "75") (pinfunction "TV_VRM_75") (pintype "passive+no_connect"))
    )
    (net (code "88") (name "unconnected-(U4-TV_VRP-Pad76)") (class "Default")
      (node (ref "U4") (pin "76") (pinfunction "TV_VRP_76") (pintype "passive+no_connect"))
    )
    (net (code "89") (name "unconnected-(U6-CTS#-Pad5)") (class "Default")
      (node (ref "U6") (pin "5") (pinfunction "CTS#_5") (pintype "passive+no_connect"))
    )
    (net (code "90") (name "unconnected-(U6-RTS#-Pad4)") (class "Default")
      (node (ref "U6") (pin "4") (pinfunction "RTS#_4") (pintype "passive+no_connect"))
    )
    (net (code "91") (name "unconnected-(U6-TNOW-Pad6)") (class "Default")
      (node (ref "U6") (pin "6") (pinfunction "TNOW_6") (pintype "passive+no_connect"))
    )
    (net (code "92") (name "unconnected-(USB2-ID-Pad4)") (class "Default")
      (node (ref "USB2") (pin "4") (pinfunction "ID_4") (pintype "passive+no_connect"))
    )
  )
)
